# power_supply.net
KiCad netlist of a schematic drawn in EAGLE
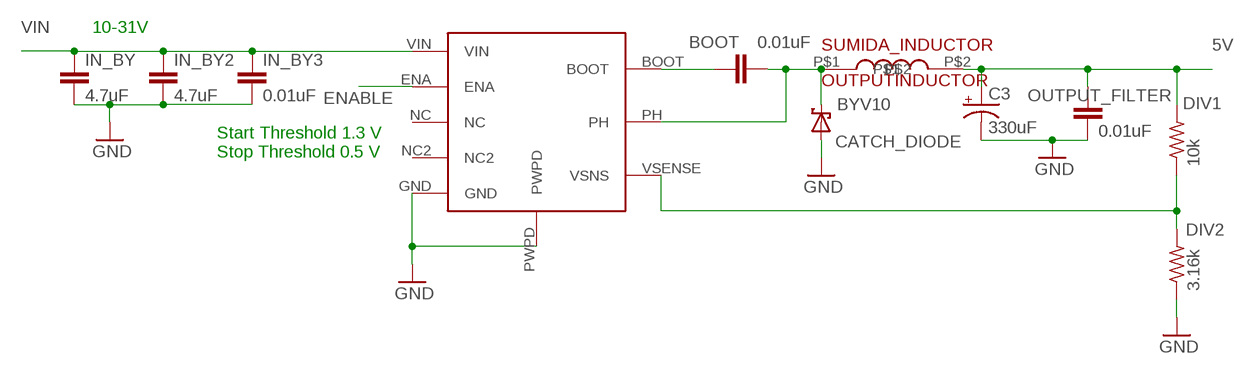
[diagram p0: schematic, sheet 1]

(export (version "E")
  (design (tool "Eeschema 10.0.6"))
  (components
    (comp (ref "BOOT")
      (value "0.01uF")
      (footprint "eagle-import:C0805")
      (libsource (lib "eagle-import") (part "C-EUC0805"))
    )
    (comp (ref "C3")
      (value "330uF")
      (footprint "eagle-import:PANASONIC_F")
      (libsource (lib "eagle-import") (part "CPOL-USF"))
    )
    (comp (ref "CATCH_DIODE")
      (value "BYV10")
      (footprint "eagle-import:DO41-10")
      (libsource (lib "eagle-import") (part "BYV10"))
    )
    (comp (ref "DIV1")
      (value "10k")
      (footprint "eagle-import:R0805")
      (libsource (lib "eagle-import") (part "R-US_R0805"))
    )
    (comp (ref "DIV2")
      (value "3.16k")
      (footprint "eagle-import:R0805")
      (libsource (lib "eagle-import") (part "R-US_R0805"))
    )
    (comp (ref "IN_BY")
      (value "4.7uF")
      (footprint "eagle-import:C0805")
      (libsource (lib "eagle-import") (part "C-EUC0805"))
    )
    (comp (ref "IN_BY2")
      (value "4.7uF")
      (footprint "eagle-import:C0805")
      (libsource (lib "eagle-import") (part "C-EUC0805"))
    )
    (comp (ref "IN_BY3")
      (value "0.01uF")
      (footprint "eagle-import:C0805")
      (libsource (lib "eagle-import") (part "C-EUC0805"))
    )
    (comp (ref "OUTPUTINDUCTOR")
      (value "SUMIDA_INDUCTOR")
      (footprint "eagle-import:SUMIDA_INDUCTOR")
      (libsource (lib "eagle-import") (part "SUMIDA_INDUCTOR"))
    )
    (comp (ref "OUTPUT_FILTER")
      (value "0.01uF")
      (footprint "eagle-import:C0805")
      (libsource (lib "eagle-import") (part "C-EUC0805"))
    )
    (comp (ref "U$1")
      (value "TPS5450")
      (footprint "eagle-import:TPS5450-Q1")
      (libsource (lib "eagle-import") (part "TPS5450"))
    )
  )
  (nets
    (net (code "1") (name "/5V") (class "Default")
      (node (ref "C3") (pin "+") (pinfunction "+_+") (pintype "passive"))
      (node (ref "DIV1") (pin "2") (pinfunction "2_2") (pintype "passive"))
      (node (ref "OUTPUTINDUCTOR") (pin "P$2") (pinfunction "P$2_P$2") (pintype "bidirectional"))
      (node (ref "OUTPUT_FILTER") (pin "1") (pinfunction "1_1") (pintype "passive"))
    )
    (net (code "2") (name "/ENABLE") (class "Default")
      (node (ref "U$1") (pin "ENA") (pinfunction "ENA_ENA") (pintype "bidirectional"))
    )
    (net (code "3") (name "/VIN") (class "Default")
      (node (ref "IN_BY") (pin "1") (pinfunction "1_1") (pintype "passive"))
      (node (ref "IN_BY2") (pin "1") (pinfunction "1_1") (pintype "passive"))
      (node (ref "IN_BY3") (pin "1") (pinfunction "1_1") (pintype "passive"))
      (node (ref "U$1") (pin "VIN") (pinfunction "VIN_VIN") (pintype "bidirectional"))
    )
    (net (code "4") (name "GND") (class "Default")
      (node (ref "C3") (pin "-") (pinfunction "-_-") (pintype "passive"))
      (node (ref "CATCH_DIODE") (pin "A") (pinfunction "A_A") (pintype "passive"))
      (node (ref "DIV2") (pin "1") (pinfunction "1_1") (pintype "passive"))
      (node (ref "IN_BY") (pin "2") (pinfunction "2_2") (pintype "passive"))
      (node (ref "IN_BY2") (pin "2") (pinfunction "2_2") (pintype "passive"))
      (node (ref "IN_BY3") (pin "2") (pinfunction "2_2") (pintype "passive"))
      (node (ref "OUTPUT_FILTER") (pin "2") (pinfunction "2_2") (pintype "passive"))
      (node (ref "U$1") (pin "GND") (pinfunction "GND_GND") (pintype "bidirectional"))
      (node (ref "U$1") (pin "PWPD") (pinfunction "PWPD_PWPD") (pintype "bidirectional"))
    )
    (net (code "5") (name "Net-(BOOT-Pad1)") (class "Default")
      (node (ref "BOOT") (pin "1") (pinfunction "1_1") (pintype "passive"))
      (node (ref "U$1") (pin "BOOT") (pinfunction "BOOT_BOOT") (pintype "bidirectional"))
    )
    (net (code "6") (name "Net-(BOOT-Pad2)") (class "Default")
      (node (ref "BOOT") (pin "2") (pinfunction "2_2") (pintype "passive"))
      (node (ref "CATCH_DIODE") (pin "C") (pinfunction "C_C") (pintype "passive"))
      (node (ref "OUTPUTINDUCTOR") (pin "P$1") (pinfunction "P$1_P$1") (pintype "bidirectional"))
      (node (ref "U$1") (pin "PH") (pinfunction "PH_PH") (pintype "bidirectional"))
    )
    (net (code "7") (name "Net-(U$1-VSNS)") (class "Default")
      (node (ref "DIV1") (pin "1") (pinfunction "1_1") (pintype "passive"))
      (node (ref "DIV2") (pin "2") (pinfunction "2_2") (pintype "passive"))
      (node (ref "U$1") (pin "VSENSE") (pinfunction "VSNS_VSENSE") (pintype "bidirectional"))
    )
    (net (code "8") (name "unconnected-(U$1-PadNC)") (class "Default")
      (node (ref "U$1") (pin "NC") (pinfunction "NC_NC") (pintype "bidirectional"))
    )
    (net (code "9") (name "unconnected-(U$1-PadNC2)") (class "Default")
      (node (ref "U$1") (pin "NC2") (pinfunction "NC2_NC2") (pintype "bidirectional"))
    )
  )
)
